# sensor-header.net
KiCad netlist of a schematic drawn in Altium Designer
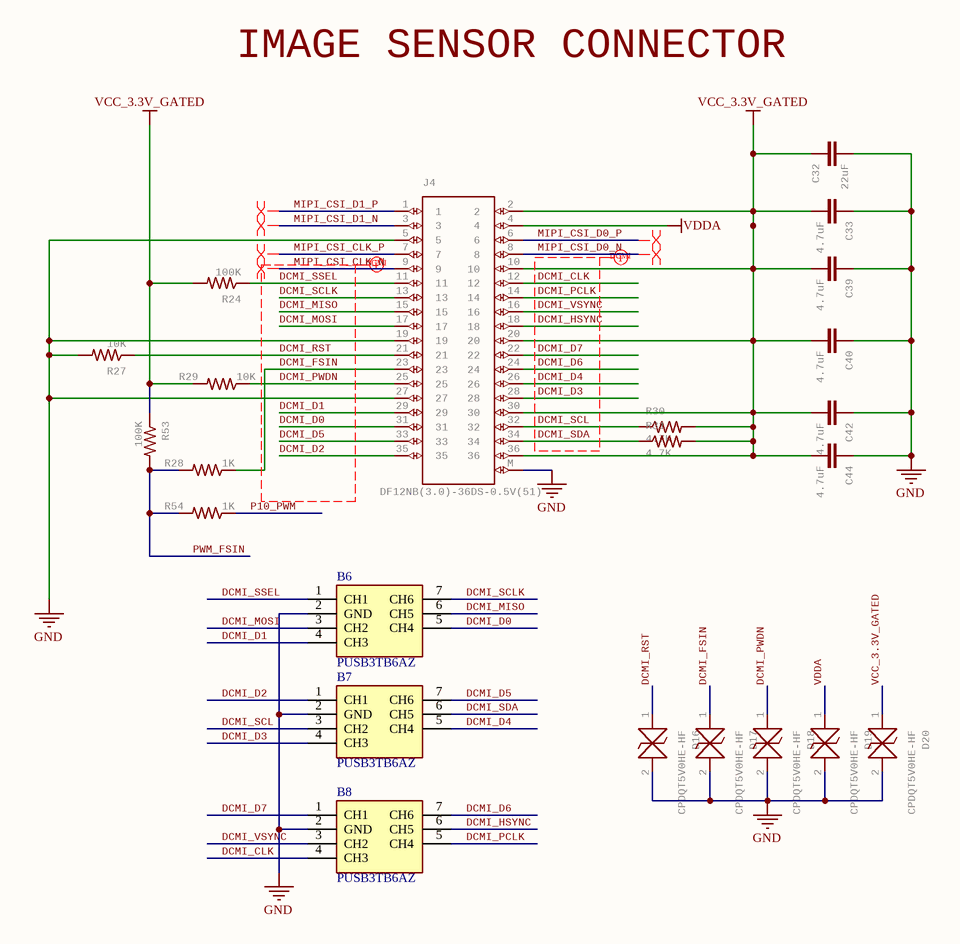
[diagram p0: sensor-header.SchDoc]

(export (version "E")
  (design (tool "Eeschema 10.0.6"))
  (components
    (comp (ref "B6")
      (value "PUSB3TB6AZ")
      (footprint "PUSB3TB6AZ")
      (description "NEXPERIA - PUSB3TB6AZ - DIODE, ESD PROTECTION, 5.5V, 0.27PF")
      (fields (field (name "MOUSER PART NUMBER") "771-PUSB3TB6AZ"))
      (libsource (lib "PUSB3TB6AZ") (part "PUSB3TB6AZ"))
    )
    (comp (ref "B7")
      (value "PUSB3TB6AZ")
      (footprint "PUSB3TB6AZ")
      (description "NEXPERIA - PUSB3TB6AZ - DIODE, ESD PROTECTION, 5.5V, 0.27PF")
      (fields (field (name "MOUSER PART NUMBER") "771-PUSB3TB6AZ"))
      (libsource (lib "PUSB3TB6AZ") (part "PUSB3TB6AZ"))
    )
    (comp (ref "B8")
      (value "PUSB3TB6AZ")
      (footprint "PUSB3TB6AZ")
      (description "NEXPERIA - PUSB3TB6AZ - DIODE, ESD PROTECTION, 5.5V, 0.27PF")
      (fields (field (name "MOUSER PART NUMBER") "771-PUSB3TB6AZ"))
      (libsource (lib "PUSB3TB6AZ") (part "PUSB3TB6AZ"))
    )
    (comp (ref "C32")
      (value "22uF")
      (footprint "0805")
      (fields (field (name "MPN") "CL21A226MQQNNNE"))
      (libsource (lib "rt10") (part "22UF-0805-6.3V-20%"))
    )
    (comp (ref "C33")
      (value "4.7uF")
      (footprint "0402-CAP")
      (description "CapacitorStandard 0603 ceramic capacitor, and 0.1\" leaded capacitor.")
      (fields (field (name "MPN") "JMK105BBJ475MV-F"))
      (libsource (lib "rt10") (part "CAP0402-CAP"))
    )
    (comp (ref "C39")
      (value "4.7uF")
      (footprint "0402-CAP")
      (description "CapacitorStandard 0603 ceramic capacitor, and 0.1\" leaded capacitor.")
      (fields (field (name "MPN") "JMK105BBJ475MV-F"))
      (libsource (lib "rt10") (part "CAP0402-CAP"))
    )
    (comp (ref "C40")
      (value "4.7uF")
      (footprint "0402-CAP")
      (description "CapacitorStandard 0603 ceramic capacitor, and 0.1\" leaded capacitor.")
      (fields (field (name "MPN") "JMK105BBJ475MV-F"))
      (libsource (lib "rt10") (part "CAP0402-CAP"))
    )
    (comp (ref "C42")
      (value "4.7uF")
      (footprint "0402-CAP")
      (description "CapacitorStandard 0603 ceramic capacitor, and 0.1\" leaded capacitor.")
      (fields (field (name "MPN") "JMK105BBJ475MV-F"))
      (libsource (lib "rt10") (part "CAP0402-CAP"))
    )
    (comp (ref "C44")
      (value "4.7uF")
      (footprint "0402-CAP")
      (description "CapacitorStandard 0603 ceramic capacitor, and 0.1\" leaded capacitor.")
      (fields (field (name "MPN") "JMK105BBJ475MV-F"))
      (libsource (lib "rt10") (part "CAP0402-CAP"))
    )
    (comp (ref "D16")
      (value "CPDQT5V0HE-HF")
      (footprint "CPDQT5V0HEHF")
      (description "ESD Suppressors / TVS Diodes DIODE ESD 5VWM 65W 0402/SOD-923F   Source:  Datasheet")
      (fields (field (name "MOUSER_PART_NUMBER") "MOUSER_PART_NUMBER"))
      (libsource (lib "rt10") (part "CPDQT5V0HE-HF"))
    )
    (comp (ref "D17")
      (value "CPDQT5V0HE-HF")
      (footprint "CPDQT5V0HEHF")
      (description "ESD Suppressors / TVS Diodes DIODE ESD 5VWM 65W 0402/SOD-923F   Source:  Datasheet")
      (fields (field (name "MOUSER_PART_NUMBER") "MOUSER_PART_NUMBER"))
      (libsource (lib "rt10") (part "CPDQT5V0HE-HF"))
    )
    (comp (ref "D18")
      (value "CPDQT5V0HE-HF")
      (footprint "CPDQT5V0HEHF")
      (description "ESD Suppressors / TVS Diodes DIODE ESD 5VWM 65W 0402/SOD-923F   Source:  Datasheet")
      (fields (field (name "MOUSER_PART_NUMBER") "MOUSER_PART_NUMBER"))
      (libsource (lib "rt10") (part "CPDQT5V0HE-HF"))
    )
    (comp (ref "D19")
      (value "CPDQT5V0HE-HF")
      (footprint "CPDQT5V0HEHF")
      (description "ESD Suppressors / TVS Diodes DIODE ESD 5VWM 65W 0402/SOD-923F   Source:  Datasheet")
      (fields (field (name "MOUSER_PART_NUMBER") "MOUSER_PART_NUMBER"))
      (libsource (lib "rt10") (part "CPDQT5V0HE-HF"))
    )
    (comp (ref "D20")
      (value "CPDQT5V0HE-HF")
      (footprint "CPDQT5V0HEHF")
      (description "ESD Suppressors / TVS Diodes DIODE ESD 5VWM 65W 0402/SOD-923F   Source:  Datasheet")
      (fields (field (name "MOUSER_PART_NUMBER") "MOUSER_PART_NUMBER"))
      (libsource (lib "rt10") (part "CPDQT5V0HE-HF"))
    )
    (comp (ref "J4")
      (value "DF12NB(3.0)-36DS-0.5V(51)")
      (footprint "DF12-36-DS")
      (description "Header")
      (libsource (lib "rt10") (part "DF12-36-DS"))
    )
    (comp (ref "R24")
      (value "100K")
      (footprint "0402-RES")
      (description "ResistorBasic schematic elements and footprints for 0603, 1206, and PTH resistors.")
      (fields (field (name "MPN") "AC0402FR-07100KL"))
      (libsource (lib "rt10") (part "RESISTOR0402-RES"))
    )
    (comp (ref "R27")
      (value "10K")
      (footprint "0402-RES")
      (description "ResistorBasic schematic elements and footprints for 0603, 1206, and PTH resistors.")
      (fields (field (name "MPN") "AC0402FR-1310K"))
      (libsource (lib "rt10") (part "RESISTOR0402-RES"))
    )
    (comp (ref "R28")
      (value "1K")
      (footprint "0402-RES")
      (description "ResistorBasic schematic elements and footprints for 0603, 1206, and PTH resistors.")
      (fields (field (name "MPN") "CRCW04021K00FKEDC"))
      (libsource (lib "rt10") (part "RESISTOR0402-RES"))
    )
    (comp (ref "R29")
      (value "10K")
      (footprint "0402-RES")
      (description "ResistorBasic schematic elements and footprints for 0603, 1206, and PTH resistors.")
      (fields (field (name "MPN") "AC0402FR-1310K"))
      (libsource (lib "rt10") (part "RESISTOR0402-RES"))
    )
    (comp (ref "R30")
      (value "4.7K")
      (footprint "0402-RES")
      (description "ResistorBasic schematic elements and footprints for 0603, 1206, and PTH resistors.")
      (fields (field (name "MPN") "AC0402FR-074K7L"))
      (libsource (lib "rt10") (part "RESISTOR0402-RES"))
    )
    (comp (ref "R31")
      (value "4.7K")
      (footprint "0402-RES")
      (description "ResistorBasic schematic elements and footprints for 0603, 1206, and PTH resistors.")
      (fields (field (name "MPN") "AC0402FR-074K7L"))
      (libsource (lib "rt10") (part "RESISTOR0402-RES"))
    )
    (comp (ref "R53")
      (value "100K")
      (footprint "0402-RES")
      (description "ResistorBasic schematic elements and footprints for 0603, 1206, and PTH resistors.")
      (fields (field (name "MPN") "AC0402FR-07100KL"))
      (libsource (lib "rt10") (part "RESISTOR0402-RES"))
    )
    (comp (ref "R54")
      (value "1K")
      (footprint "0402-RES")
      (description "ResistorBasic schematic elements and footprints for 0603, 1206, and PTH resistors.")
      (fields (field (name "MPN") "CRCW04021K00FKEDC"))
      (libsource (lib "rt10") (part "RESISTOR0402-RES"))
    )
  )
  (nets
    (net (code "1") (name "/DCMI_CLK") (class "Default")
      (node (ref "B8") (pin "4") (pinfunction "CH3_4") (pintype "passive"))
      (node (ref "J4") (pin "12") (pinfunction "12_12") (pintype "bidirectional"))
    )
    (net (code "2") (name "/DCMI_D0") (class "Default")
      (node (ref "B6") (pin "5") (pinfunction "CH4_5") (pintype "passive"))
      (node (ref "J4") (pin "31") (pinfunction "31_31") (pintype "bidirectional"))
    )
    (net (code "3") (name "/DCMI_D1") (class "Default")
      (node (ref "B6") (pin "4") (pinfunction "CH3_4") (pintype "passive"))
      (node (ref "J4") (pin "29") (pinfunction "29_29") (pintype "bidirectional"))
    )
    (net (code "4") (name "/DCMI_D2") (class "Default")
      (node (ref "B7") (pin "1") (pinfunction "CH1_1") (pintype "passive"))
      (node (ref "J4") (pin "35") (pinfunction "35_35") (pintype "bidirectional"))
    )
    (net (code "5") (name "/DCMI_D3") (class "Default")
      (node (ref "B7") (pin "4") (pinfunction "CH3_4") (pintype "passive"))
      (node (ref "J4") (pin "28") (pinfunction "28_28") (pintype "bidirectional"))
    )
    (net (code "6") (name "/DCMI_D4") (class "Default")
      (node (ref "B7") (pin "5") (pinfunction "CH4_5") (pintype "passive"))
      (node (ref "J4") (pin "26") (pinfunction "26_26") (pintype "bidirectional"))
    )
    (net (code "7") (name "/DCMI_D5") (class "Default")
      (node (ref "B7") (pin "7") (pinfunction "CH6_7") (pintype "passive"))
      (node (ref "J4") (pin "33") (pinfunction "33_33") (pintype "bidirectional"))
    )
    (net (code "8") (name "/DCMI_D6") (class "Default")
      (node (ref "B8") (pin "7") (pinfunction "CH6_7") (pintype "passive"))
      (node (ref "J4") (pin "24") (pinfunction "24_24") (pintype "bidirectional"))
    )
    (net (code "9") (name "/DCMI_D7") (class "Default")
      (node (ref "B8") (pin "1") (pinfunction "CH1_1") (pintype "passive"))
      (node (ref "J4") (pin "22") (pinfunction "22_22") (pintype "bidirectional"))
    )
    (net (code "10") (name "/DCMI_FSIN") (class "Default")
      (node (ref "D17") (pin "1") (pinfunction "1_1") (pintype "bidirectional"))
      (node (ref "J4") (pin "23") (pinfunction "23_23") (pintype "bidirectional"))
      (node (ref "R28") (pin "1") (pinfunction "1_1") (pintype "passive"))
    )
    (net (code "11") (name "/DCMI_HSYNC") (class "Default")
      (node (ref "B8") (pin "6") (pinfunction "CH5_6") (pintype "passive"))
      (node (ref "J4") (pin "18") (pinfunction "18_18") (pintype "bidirectional"))
    )
    (net (code "12") (name "/DCMI_MISO") (class "Default")
      (node (ref "B6") (pin "6") (pinfunction "CH5_6") (pintype "passive"))
      (node (ref "J4") (pin "15") (pinfunction "15_15") (pintype "bidirectional"))
    )
    (net (code "13") (name "/DCMI_MOSI") (class "Default")
      (node (ref "B6") (pin "3") (pinfunction "CH2_3") (pintype "passive"))
      (node (ref "J4") (pin "17") (pinfunction "17_17") (pintype "bidirectional"))
    )
    (net (code "14") (name "/DCMI_PCLK") (class "Default")
      (node (ref "B8") (pin "5") (pinfunction "CH4_5") (pintype "passive"))
      (node (ref "J4") (pin "14") (pinfunction "14_14") (pintype "bidirectional"))
    )
    (net (code "15") (name "/DCMI_PWDN") (class "Default")
      (node (ref "D18") (pin "1") (pinfunction "1_1") (pintype "bidirectional"))
      (node (ref "J4") (pin "25") (pinfunction "25_25") (pintype "bidirectional"))
      (node (ref "R29") (pin "1") (pinfunction "1_1") (pintype "passive"))
    )
    (net (code "16") (name "/DCMI_RST") (class "Default")
      (node (ref "D16") (pin "1") (pinfunction "1_1") (pintype "bidirectional"))
      (node (ref "J4") (pin "21") (pinfunction "21_21") (pintype "bidirectional"))
      (node (ref "R27") (pin "1") (pinfunction "1_1") (pintype "passive"))
    )
    (net (code "17") (name "/DCMI_SCL") (class "Default")
      (node (ref "B7") (pin "3") (pinfunction "CH2_3") (pintype "passive"))
      (node (ref "J4") (pin "32") (pinfunction "32_32") (pintype "bidirectional"))
      (node (ref "R30") (pin "1") (pinfunction "1_1") (pintype "passive"))
    )
    (net (code "18") (name "/DCMI_SCLK") (class "Default")
      (node (ref "B6") (pin "7") (pinfunction "CH6_7") (pintype "passive"))
      (node (ref "J4") (pin "13") (pinfunction "13_13") (pintype "bidirectional"))
    )
    (net (code "19") (name "/DCMI_SDA") (class "Default")
      (node (ref "B7") (pin "6") (pinfunction "CH5_6") (pintype "passive"))
      (node (ref "J4") (pin "34") (pinfunction "34_34") (pintype "bidirectional"))
      (node (ref "R31") (pin "1") (pinfunction "1_1") (pintype "passive"))
    )
    (net (code "20") (name "/DCMI_SSEL") (class "Default")
      (node (ref "B6") (pin "1") (pinfunction "CH1_1") (pintype "passive"))
      (node (ref "J4") (pin "11") (pinfunction "11_11") (pintype "bidirectional"))
      (node (ref "R24") (pin "1") (pinfunction "1_1") (pintype "passive"))
    )
    (net (code "21") (name "/DCMI_VSYNC") (class "Default")
      (node (ref "B8") (pin "3") (pinfunction "CH2_3") (pintype "passive"))
      (node (ref "J4") (pin "16") (pinfunction "16_16") (pintype "bidirectional"))
    )
    (net (code "22") (name "/MIPI_CSI_CLK_N") (class "Default")
      (node (ref "J4") (pin "9") (pinfunction "9_9") (pintype "bidirectional"))
    )
    (net (code "23") (name "/MIPI_CSI_CLK_P") (class "Default")
      (node (ref "J4") (pin "7") (pinfunction "7_7") (pintype "bidirectional"))
    )
    (net (code "24") (name "/MIPI_CSI_D0_N") (class "Default")
      (node (ref "J4") (pin "8") (pinfunction "8_8") (pintype "bidirectional"))
    )
    (net (code "25") (name "/MIPI_CSI_D0_P") (class "Default")
      (node (ref "J4") (pin "6") (pinfunction "6_6") (pintype "bidirectional"))
    )
    (net (code "26") (name "/MIPI_CSI_D1_N") (class "Default")
      (node (ref "J4") (pin "3") (pinfunction "3_3") (pintype "bidirectional"))
    )
    (net (code "27") (name "/MIPI_CSI_D1_P") (class "Default")
      (node (ref "J4") (pin "1") (pinfunction "1_1") (pintype "bidirectional"))
    )
    (net (code "28") (name "/P10_PWM") (class "Default")
      (node (ref "R54") (pin "1") (pinfunction "1_1") (pintype "passive"))
    )
    (net (code "29") (name "/PWM_FSIN") (class "Default")
      (node (ref "R28") (pin "2") (pinfunction "2_2") (pintype "passive"))
      (node (ref "R53") (pin "2") (pinfunction "2_2") (pintype "passive"))
      (node (ref "R54") (pin "2") (pinfunction "2_2") (pintype "passive"))
    )
    (net (code "30") (name "GND") (class "Default")
      (node (ref "B6") (pin "2") (pinfunction "GND_2") (pintype "passive"))
      (node (ref "B7") (pin "2") (pinfunction "GND_2") (pintype "passive"))
      (node (ref "B8") (pin "2") (pinfunction "GND_2") (pintype "passive"))
      (node (ref "C32") (pin "2") (pinfunction "2_2") (pintype "passive"))
      (node (ref "C33") (pin "1") (pinfunction "1_1") (pintype "passive"))
      (node (ref "C39") (pin "1") (pinfunction "1_1") (pintype "passive"))
      (node (ref "C40") (pin "1") (pinfunction "1_1") (pintype "passive"))
      (node (ref "C42") (pin "1") (pinfunction "1_1") (pintype "passive"))
      (node (ref "C44") (pin "1") (pinfunction "1_1") (pintype "passive"))
      (node (ref "D16") (pin "2") (pinfunction "2_2") (pintype "bidirectional"))
      (node (ref "D17") (pin "2") (pinfunction "2_2") (pintype "bidirectional"))
      (node (ref "D18") (pin "2") (pinfunction "2_2") (pintype "bidirectional"))
      (node (ref "D19") (pin "2") (pinfunction "2_2") (pintype "bidirectional"))
      (node (ref "D20") (pin "2") (pinfunction "2_2") (pintype "bidirectional"))
      (node (ref "J4") (pin "19") (pinfunction "19_19") (pintype "bidirectional"))
      (node (ref "J4") (pin "27") (pinfunction "27_27") (pintype "bidirectional"))
      (node (ref "J4") (pin "5") (pinfunction "5_5") (pintype "bidirectional"))
      (node (ref "J4") (pin "M") (pinfunction "M_M") (pintype "bidirectional"))
      (node (ref "R27") (pin "2") (pinfunction "2_2") (pintype "passive"))
    )
    (net (code "31") (name "VCC_3.3V_GATED") (class "Default")
      (node (ref "C32") (pin "1") (pinfunction "1_1") (pintype "passive"))
      (node (ref "C33") (pin "2") (pinfunction "2_2") (pintype "passive"))
      (node (ref "C39") (pin "2") (pinfunction "2_2") (pintype "passive"))
      (node (ref "C40") (pin "2") (pinfunction "2_2") (pintype "passive"))
      (node (ref "C42") (pin "2") (pinfunction "2_2") (pintype "passive"))
      (node (ref "C44") (pin "2") (pinfunction "2_2") (pintype "passive"))
      (node (ref "D20") (pin "1") (pinfunction "1_1") (pintype "bidirectional"))
      (node (ref "J4") (pin "10") (pinfunction "10_10") (pintype "bidirectional"))
      (node (ref "J4") (pin "2") (pinfunction "2_2") (pintype "bidirectional"))
      (node (ref "J4") (pin "20") (pinfunction "20_20") (pintype "bidirectional"))
      (node (ref "J4") (pin "30") (pinfunction "30_30") (pintype "bidirectional"))
      (node (ref "J4") (pin "36") (pinfunction "36_36") (pintype "bidirectional"))
      (node (ref "R24") (pin "2") (pinfunction "2_2") (pintype "passive"))
      (node (ref "R29") (pin "2") (pinfunction "2_2") (pintype "passive"))
      (node (ref "R30") (pin "2") (pinfunction "2_2") (pintype "passive"))
      (node (ref "R31") (pin "2") (pinfunction "2_2") (pintype "passive"))
      (node (ref "R53") (pin "1") (pinfunction "1_1") (pintype "passive"))
    )
    (net (code "32") (name "VDDA") (class "Default")
      (node (ref "D19") (pin "1") (pinfunction "1_1") (pintype "bidirectional"))
      (node (ref "J4") (pin "4") (pinfunction "4_4") (pintype "bidirectional"))
    )
  )
)
